# Interface.net
KiCad netlist of a schematic drawn in Altium Designer
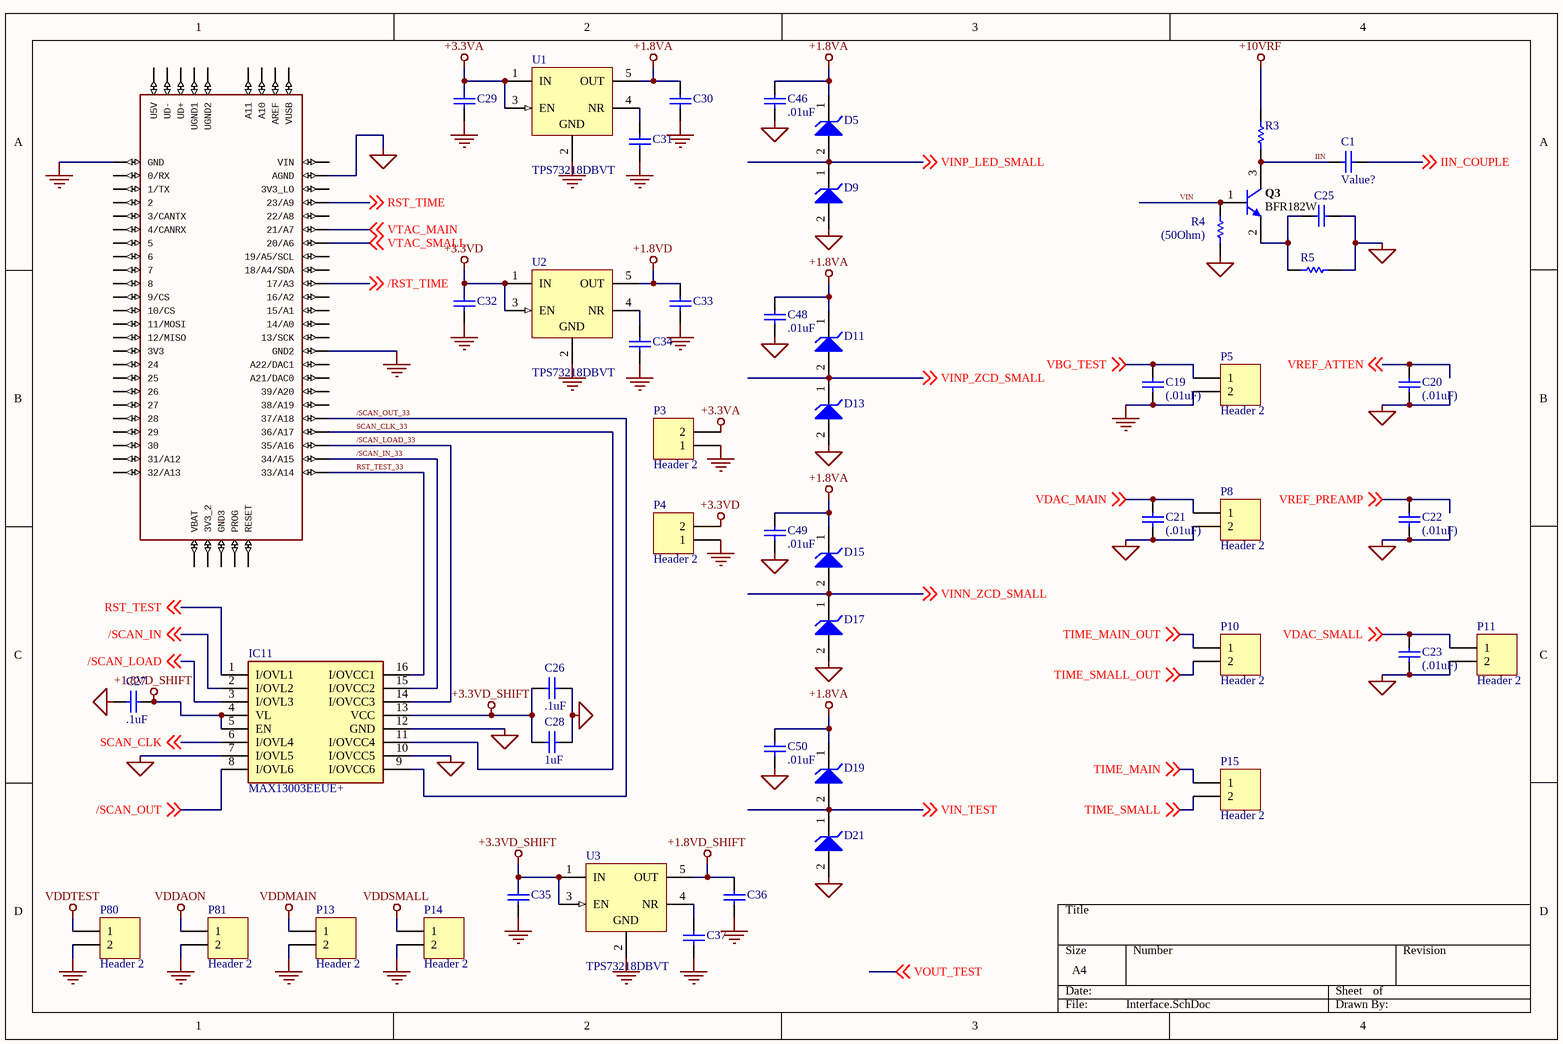
[diagram p0: Interface.SchDoc]

(export (version "E")
  (design (tool "Eeschema 10.0.6"))
  (components
    (comp (ref "1")
      (value "TEENSY_3.5/3.6")
      (footprint "TEENSY_3.5/3.6")
      (libsource (lib "Teensy356") (part "TEENSY_3.5/3.6"))
    )
    (comp (ref "C1")
      (value "Value?")
      (footprint "CAPC2013X140X45NL15T25")
      (description "0402")
      (fields (field (name "PART NUMBER") "GRM21BR71A106KE51L") (field (name "MANUFACTURER") "Murata"))
      (libsource (lib "Altium Content Vault") (part "CAP"))
    )
    (comp (ref "C19")
      (value "(.01uF)")
      (footprint "CAPC2013X140X45NL15T25")
      (description "0402")
      (fields (field (name "PART NUMBER") "GRM21BR71A106KE51L") (field (name "MANUFACTURER") "Murata"))
      (libsource (lib "Altium Content Vault") (part "CAP"))
    )
    (comp (ref "C20")
      (value "(.01uF)")
      (footprint "CAPC2013X140X45NL15T25")
      (description "0402")
      (fields (field (name "PART NUMBER") "GRM21BR71A106KE51L") (field (name "MANUFACTURER") "Murata"))
      (libsource (lib "Altium Content Vault") (part "CAP"))
    )
    (comp (ref "C21")
      (value "(.01uF)")
      (footprint "CAPC2013X140X45NL15T25")
      (description "0402")
      (fields (field (name "PART NUMBER") "GRM21BR71A106KE51L") (field (name "MANUFACTURER") "Murata"))
      (libsource (lib "Altium Content Vault") (part "CAP"))
    )
    (comp (ref "C22")
      (value "(.01uF)")
      (footprint "CAPC2013X140X45NL15T25")
      (description "0402")
      (fields (field (name "PART NUMBER") "GRM21BR71A106KE51L") (field (name "MANUFACTURER") "Murata"))
      (libsource (lib "Altium Content Vault") (part "CAP"))
    )
    (comp (ref "C23")
      (value "(.01uF)")
      (footprint "CAPC2013X140X45NL15T25")
      (description "0402")
      (fields (field (name "PART NUMBER") "GRM21BR71A106KE51L") (field (name "MANUFACTURER") "Murata"))
      (libsource (lib "Altium Content Vault") (part "CAP"))
    )
    (comp (ref "C25")
      (value "~")
      (footprint "CAPC2013X140X45NL15T25")
      (description "0402")
      (fields (field (name "PART NUMBER") "GRM21BR71A106KE51L") (field (name "MANUFACTURER") "Murata"))
      (libsource (lib "Altium Content Vault") (part "CAP"))
    )
    (comp (ref "C26")
      (value ".1uF")
      (footprint "CAPC2013X140X45NL15T25")
      (description "0402")
      (fields (field (name "PART NUMBER") "GRM21BR71A106KE51L") (field (name "MANUFACTURER") "Murata"))
      (libsource (lib "Altium Content Vault") (part "CAP"))
    )
    (comp (ref "C27")
      (value ".1uF")
      (footprint "CAPC2013X140X45NL15T25")
      (description "0402")
      (fields (field (name "PART NUMBER") "GRM21BR71A106KE51L") (field (name "MANUFACTURER") "Murata"))
      (libsource (lib "Altium Content Vault") (part "CAP"))
    )
    (comp (ref "C28")
      (value "1uF")
      (footprint "CAPC2013X140X45NL15T25")
      (description "0402")
      (fields (field (name "PART NUMBER") "GRM21BR71A106KE51L") (field (name "MANUFACTURER") "Murata"))
      (libsource (lib "Altium Content Vault") (part "CAP"))
    )
    (comp (ref "C29")
      (value "~")
      (footprint "CAPC2013X140X45NL15T25")
      (description "0402")
      (fields (field (name "PART NUMBER") "GRM21BR71A106KE51L") (field (name "MANUFACTURER") "Murata"))
      (libsource (lib "Altium Content Vault") (part "CAP"))
    )
    (comp (ref "C30")
      (value "~")
      (footprint "CAPC2013X140X45NL15T25")
      (description "0402")
      (fields (field (name "PART NUMBER") "GRM21BR71A106KE51L") (field (name "MANUFACTURER") "Murata"))
      (libsource (lib "Altium Content Vault") (part "CAP"))
    )
    (comp (ref "C31")
      (value "~")
      (footprint "CAPC2013X140X45NL15T25")
      (description "0402")
      (fields (field (name "PART NUMBER") "GRM21BR71A106KE51L") (field (name "MANUFACTURER") "Murata"))
      (libsource (lib "Altium Content Vault") (part "CAP"))
    )
    (comp (ref "C32")
      (value "~")
      (footprint "CAPC2013X140X45NL15T25")
      (description "0402")
      (fields (field (name "PART NUMBER") "GRM21BR71A106KE51L") (field (name "MANUFACTURER") "Murata"))
      (libsource (lib "Altium Content Vault") (part "CAP"))
    )
    (comp (ref "C33")
      (value "~")
      (footprint "CAPC2013X140X45NL15T25")
      (description "0402")
      (fields (field (name "PART NUMBER") "GRM21BR71A106KE51L") (field (name "MANUFACTURER") "Murata"))
      (libsource (lib "Altium Content Vault") (part "CAP"))
    )
    (comp (ref "C34")
      (value "~")
      (footprint "CAPC2013X140X45NL15T25")
      (description "0402")
      (fields (field (name "PART NUMBER") "GRM21BR71A106KE51L") (field (name "MANUFACTURER") "Murata"))
      (libsource (lib "Altium Content Vault") (part "CAP"))
    )
    (comp (ref "C35")
      (value "~")
      (footprint "CAPC2013X140X45NL15T25")
      (description "0402")
      (fields (field (name "PART NUMBER") "GRM21BR71A106KE51L") (field (name "MANUFACTURER") "Murata"))
      (libsource (lib "Altium Content Vault") (part "CAP"))
    )
    (comp (ref "C36")
      (value "~")
      (footprint "CAPC2013X140X45NL15T25")
      (description "0402")
      (fields (field (name "PART NUMBER") "GRM21BR71A106KE51L") (field (name "MANUFACTURER") "Murata"))
      (libsource (lib "Altium Content Vault") (part "CAP"))
    )
    (comp (ref "C37")
      (value "~")
      (footprint "CAPC2013X140X45NL15T25")
      (description "0402")
      (fields (field (name "PART NUMBER") "GRM21BR71A106KE51L") (field (name "MANUFACTURER") "Murata"))
      (libsource (lib "Altium Content Vault") (part "CAP"))
    )
    (comp (ref "C46")
      (value ".01uF")
      (footprint "CAPC2013X140X45NL15T25")
      (description "0402")
      (fields (field (name "PART NUMBER") "GRM21BR71A106KE51L") (field (name "MANUFACTURER") "Murata"))
      (libsource (lib "Altium Content Vault") (part "CAP"))
    )
    (comp (ref "C48")
      (value ".01uF")
      (footprint "CAPC2013X140X45NL15T25")
      (description "0402")
      (fields (field (name "PART NUMBER") "GRM21BR71A106KE51L") (field (name "MANUFACTURER") "Murata"))
      (libsource (lib "Altium Content Vault") (part "CAP"))
    )
    (comp (ref "C49")
      (value ".01uF")
      (footprint "CAPC2013X140X45NL15T25")
      (description "0402")
      (fields (field (name "PART NUMBER") "GRM21BR71A106KE51L") (field (name "MANUFACTURER") "Murata"))
      (libsource (lib "Altium Content Vault") (part "CAP"))
    )
    (comp (ref "C50")
      (value ".01uF")
      (footprint "CAPC2013X140X45NL15T25")
      (description "0402")
      (fields (field (name "PART NUMBER") "GRM21BR71A106KE51L") (field (name "MANUFACTURER") "Murata"))
      (libsource (lib "Altium Content Vault") (part "CAP"))
    )
    (comp (ref "D5")
      (value "~")
      (footprint "ONSC-SOD-123-2-425-04_V")
      (description "Zener Voltage Regulator, 2-Pin SOD-123, Pb-Free, Tape and Reel")
      (fields (field (name "MANUFACTURER") "On Semiconductor") (field (name "PARTNUMBER") "MMSZ4679T1G"))
      (libsource (lib "Altium Content Vault") (part "ONSC-K1A2-2"))
    )
    (comp (ref "D9")
      (value "~")
      (footprint "ONSC-SOD-123-2-425-04_V")
      (description "Zener Voltage Regulator, 2-Pin SOD-123, Pb-Free, Tape and Reel")
      (fields (field (name "MANUFACTURER") "On Semiconductor") (field (name "PARTNUMBER") "MMSZ4679T1G"))
      (libsource (lib "Altium Content Vault") (part "ONSC-K1A2-2"))
    )
    (comp (ref "D11")
      (value "~")
      (footprint "ONSC-SOD-123-2-425-04_V")
      (description "Zener Voltage Regulator, 2-Pin SOD-123, Pb-Free, Tape and Reel")
      (fields (field (name "MANUFACTURER") "On Semiconductor") (field (name "PARTNUMBER") "MMSZ4679T1G"))
      (libsource (lib "Altium Content Vault") (part "ONSC-K1A2-2"))
    )
    (comp (ref "D13")
      (value "~")
      (footprint "ONSC-SOD-123-2-425-04_V")
      (description "Zener Voltage Regulator, 2-Pin SOD-123, Pb-Free, Tape and Reel")
      (fields (field (name "MANUFACTURER") "On Semiconductor") (field (name "PARTNUMBER") "MMSZ4679T1G"))
      (libsource (lib "Altium Content Vault") (part "ONSC-K1A2-2"))
    )
    (comp (ref "D15")
      (value "~")
      (footprint "ONSC-SOD-123-2-425-04_V")
      (description "Zener Voltage Regulator, 2-Pin SOD-123, Pb-Free, Tape and Reel")
      (fields (field (name "MANUFACTURER") "On Semiconductor") (field (name "PARTNUMBER") "MMSZ4679T1G"))
      (libsource (lib "Altium Content Vault") (part "ONSC-K1A2-2"))
    )
    (comp (ref "D17")
      (value "~")
      (footprint "ONSC-SOD-123-2-425-04_V")
      (description "Zener Voltage Regulator, 2-Pin SOD-123, Pb-Free, Tape and Reel")
      (fields (field (name "MANUFACTURER") "On Semiconductor") (field (name "PARTNUMBER") "MMSZ4679T1G"))
      (libsource (lib "Altium Content Vault") (part "ONSC-K1A2-2"))
    )
    (comp (ref "D19")
      (value "~")
      (footprint "ONSC-SOD-123-2-425-04_V")
      (description "Zener Voltage Regulator, 2-Pin SOD-123, Pb-Free, Tape and Reel")
      (fields (field (name "MANUFACTURER") "On Semiconductor") (field (name "PARTNUMBER") "MMSZ4679T1G"))
      (libsource (lib "Altium Content Vault") (part "ONSC-K1A2-2"))
    )
    (comp (ref "D21")
      (value "~")
      (footprint "ONSC-SOD-123-2-425-04_V")
      (description "Zener Voltage Regulator, 2-Pin SOD-123, Pb-Free, Tape and Reel")
      (fields (field (name "MANUFACTURER") "On Semiconductor") (field (name "PARTNUMBER") "MMSZ4679T1G"))
      (libsource (lib "Altium Content Vault") (part "ONSC-K1A2-2"))
    )
    (comp (ref "IC11")
      (value "MAX13003EEUE+")
      (footprint "SamacSys:SOP65P640X110-16N")
      (description "Integrated Circuit")
      (libsource (lib "*") (part "MAX13003EEUE+"))
    )
    (comp (ref "P3")
      (value "Header 2")
      (footprint "HDR1X2")
      (description "Header, 2-Pin")
      (fields (field (name "PUBLISHER") "Altium Limited"))
      (libsource (lib "Miscellaneous Connectors") (part "Header 2"))
    )
    (comp (ref "P4")
      (value "Header 2")
      (footprint "HDR1X2")
      (description "Header, 2-Pin")
      (fields (field (name "PUBLISHER") "Altium Limited"))
      (libsource (lib "Miscellaneous Connectors") (part "Header 2"))
    )
    (comp (ref "P5")
      (value "Header 2")
      (footprint "HDR1X2")
      (description "Header, 2-Pin")
      (fields (field (name "PUBLISHER") "Altium Limited"))
      (libsource (lib "") (part "Header 2_1"))
    )
    (comp (ref "P8")
      (value "Header 2")
      (footprint "HDR1X2")
      (description "Header, 2-Pin")
      (fields (field (name "PUBLISHER") "Altium Limited"))
      (libsource (lib "") (part "Header 2_1"))
    )
    (comp (ref "P10")
      (value "Header 2")
      (footprint "HDR1X2")
      (description "Header, 2-Pin")
      (fields (field (name "PUBLISHER") "Altium Limited"))
      (libsource (lib "") (part "Header 2_1"))
    )
    (comp (ref "P11")
      (value "Header 2")
      (footprint "HDR1X2")
      (description "Header, 2-Pin")
      (fields (field (name "PUBLISHER") "Altium Limited"))
      (libsource (lib "") (part "Header 2_1"))
    )
    (comp (ref "P13")
      (value "Header 2")
      (footprint "HDR1X2")
      (description "Header, 2-Pin")
      (fields (field (name "PUBLISHER") "Altium Limited"))
      (libsource (lib "") (part "Header 2_1"))
    )
    (comp (ref "P14")
      (value "Header 2")
      (footprint "HDR1X2")
      (description "Header, 2-Pin")
      (fields (field (name "PUBLISHER") "Altium Limited"))
      (libsource (lib "") (part "Header 2_1"))
    )
    (comp (ref "P15")
      (value "Header 2")
      (footprint "HDR1X2")
      (description "Header, 2-Pin")
      (fields (field (name "PUBLISHER") "Altium Limited"))
      (libsource (lib "") (part "Header 2_1"))
    )
    (comp (ref "P80")
      (value "Header 2")
      (footprint "HDR1X2")
      (description "Header, 2-Pin")
      (fields (field (name "PUBLISHER") "Altium Limited"))
      (libsource (lib "") (part "Header 2_1"))
    )
    (comp (ref "P81")
      (value "Header 2")
      (footprint "HDR1X2")
      (description "Header, 2-Pin")
      (fields (field (name "PUBLISHER") "Altium Limited"))
      (libsource (lib "") (part "Header 2_1"))
    )
    (comp (ref "Q3")
      (value "BFR182W")
      (footprint "INF-SOT323_L")
      (description "NPN Silicon RF Transistor, 12 V VCEO, 35 mA IC, 19 dB Gmax, SOT323, Green")
      (fields (field (name "MANUFACTURER") "Infineon"))
      (libsource (lib "Altium Content Vault") (part "INF-BFR182W-3"))
    )
    (comp (ref "R3")
      (value "~")
      (footprint "RESC1005X40X25NL05T10")
      (description "0402")
      (fields (field (name "PART NUMBER") "RC0402FR-071KL") (field (name "MANUFACTURER") "Yageo / Phycomp"))
      (libsource (lib "Altium Content Vault") (part "RES"))
    )
    (comp (ref "R4")
      (value "(50Ohm)")
      (footprint "RESC1005X40X25NL05T10")
      (description "0402")
      (fields (field (name "PART NUMBER") "RC0402FR-071KL") (field (name "MANUFACTURER") "Yageo / Phycomp"))
      (libsource (lib "Altium Content Vault") (part "RES"))
    )
    (comp (ref "R5")
      (value "~")
      (footprint "RESC1005X40X25NL05T10")
      (description "0402")
      (fields (field (name "PART NUMBER") "RC0402FR-071KL") (field (name "MANUFACTURER") "Yageo / Phycomp"))
      (libsource (lib "Altium Content Vault") (part "RES"))
    )
    (comp (ref "U1")
      (value "TPS73218DBVT")
      (footprint "DBV0005A_N")
      (fields (field (name "MANUFACTURER") "Texas Instruments"))
      (libsource (lib "Altium Content Vault") (part "TI-TPS79NXX-YYSOT5"))
    )
    (comp (ref "U2")
      (value "TPS73218DBVT")
      (footprint "DBV0005A_N")
      (fields (field (name "MANUFACTURER") "Texas Instruments"))
      (libsource (lib "Altium Content Vault") (part "TI-TPS79NXX-YYSOT5"))
    )
    (comp (ref "U3")
      (value "TPS73218DBVT")
      (footprint "DBV0005A_N")
      (fields (field (name "MANUFACTURER") "Texas Instruments"))
      (libsource (lib "Altium Content Vault") (part "TI-TPS79NXX-YYSOT5"))
    )
  )
  (nets
    (net (code "1") (name "+1.8VA") (class "Default")
      (node (ref "C30") (pin "2") (pinfunction "2_2") (pintype "passive"))
      (node (ref "C46") (pin "2") (pinfunction "2_2") (pintype "passive"))
      (node (ref "C48") (pin "2") (pinfunction "2_2") (pintype "passive"))
      (node (ref "C49") (pin "2") (pinfunction "2_2") (pintype "passive"))
      (node (ref "C50") (pin "2") (pinfunction "2_2") (pintype "passive"))
      (node (ref "D11") (pin "1") (pinfunction "K_1") (pintype "passive"))
      (node (ref "D15") (pin "1") (pinfunction "K_1") (pintype "passive"))
      (node (ref "D19") (pin "1") (pinfunction "K_1") (pintype "passive"))
      (node (ref "D5") (pin "1") (pinfunction "K_1") (pintype "passive"))
      (node (ref "U1") (pin "5") (pinfunction "OUT_5") (pintype "power_in"))
    )
    (net (code "2") (name "+1.8VD") (class "Default")
      (node (ref "C33") (pin "2") (pinfunction "2_2") (pintype "passive"))
      (node (ref "U2") (pin "5") (pinfunction "OUT_5") (pintype "power_in"))
    )
    (net (code "3") (name "+1.8VD_SHIFT") (class "Default")
      (node (ref "C27") (pin "1") (pinfunction "1_1") (pintype "passive"))
      (node (ref "C36") (pin "2") (pinfunction "2_2") (pintype "passive"))
      (node (ref "IC11") (pin "4") (pinfunction "VL_4") (pintype "passive"))
      (node (ref "IC11") (pin "5") (pinfunction "EN_5") (pintype "passive"))
      (node (ref "U3") (pin "5") (pinfunction "OUT_5") (pintype "power_in"))
    )
    (net (code "4") (name "+3.3VA") (class "Default")
      (node (ref "C29") (pin "2") (pinfunction "2_2") (pintype "passive"))
      (node (ref "P3") (pin "2") (pinfunction "2_2") (pintype "passive"))
      (node (ref "U1") (pin "1") (pinfunction "IN_1") (pintype "power_in"))
      (node (ref "U1") (pin "3") (pinfunction "EN_3") (pintype "input"))
    )
    (net (code "5") (name "+3.3VD") (class "Default")
      (node (ref "C32") (pin "2") (pinfunction "2_2") (pintype "passive"))
      (node (ref "P4") (pin "2") (pinfunction "2_2") (pintype "passive"))
      (node (ref "U2") (pin "1") (pinfunction "IN_1") (pintype "power_in"))
      (node (ref "U2") (pin "3") (pinfunction "EN_3") (pintype "input"))
    )
    (net (code "6") (name "+3.3VD_SHIFT") (class "Default")
      (node (ref "C26") (pin "2") (pinfunction "2_2") (pintype "passive"))
      (node (ref "C28") (pin "2") (pinfunction "2_2") (pintype "passive"))
      (node (ref "C35") (pin "2") (pinfunction "2_2") (pintype "passive"))
      (node (ref "IC11") (pin "13") (pinfunction "VCC_13") (pintype "passive"))
      (node (ref "U3") (pin "1") (pinfunction "IN_1") (pintype "power_in"))
      (node (ref "U3") (pin "3") (pinfunction "EN_3") (pintype "input"))
    )
    (net (code "7") (name "+10VRF") (class "Default")
      (node (ref "R3") (pin "1") (pinfunction "1_1") (pintype "passive"))
    )
    (net (code "8") (name "/IIN") (class "Default")
      (node (ref "C1") (pin "1") (pinfunction "1_1") (pintype "passive"))
      (node (ref "Q3") (pin "3") (pinfunction "C_3") (pintype "passive"))
      (node (ref "R3") (pin "2") (pinfunction "2_2") (pintype "passive"))
    )
    (net (code "9") (name "/RST_TEST_33") (class "Default")
      (node (ref "1") (pin "33/A14") (pinfunction "33/A14_33/A14") (pintype "bidirectional"))
      (node (ref "IC11") (pin "16") (pinfunction "I/OVCC1_16") (pintype "passive"))
    )
    (net (code "10") (name "/SCAN_CLK_33") (class "Default")
      (node (ref "1") (pin "36/A17") (pinfunction "36/A17_36/A17") (pintype "bidirectional"))
      (node (ref "IC11") (pin "11") (pinfunction "I/OVCC4_11") (pintype "passive"))
    )
    (net (code "11") (name "/VIN") (class "Default")
      (node (ref "Q3") (pin "1") (pinfunction "B_1") (pintype "passive"))
      (node (ref "R4") (pin "2") (pinfunction "2_2") (pintype "passive"))
    )
    (net (code "12") (name "/{slash}SCAN_IN_33") (class "Default")
      (node (ref "1") (pin "34/A15") (pinfunction "34/A15_34/A15") (pintype "bidirectional"))
      (node (ref "IC11") (pin "15") (pinfunction "I/OVCC2_15") (pintype "passive"))
    )
    (net (code "13") (name "/{slash}SCAN_LOAD_33") (class "Default")
      (node (ref "1") (pin "35/A16") (pinfunction "35/A16_35/A16") (pintype "bidirectional"))
      (node (ref "IC11") (pin "14") (pinfunction "I/OVCC3_14") (pintype "passive"))
    )
    (net (code "14") (name "/{slash}SCAN_OUT_33") (class "Default")
      (node (ref "1") (pin "37/A18") (pinfunction "37/A18_37/A18") (pintype "bidirectional"))
      (node (ref "IC11") (pin "9") (pinfunction "I/OVCC6_9") (pintype "passive"))
    )
    (net (code "15") (name "GND") (class "Default")
      (node (ref "1") (pin "AGND") (pinfunction "AGND_AGND") (pintype "bidirectional"))
      (node (ref "1") (pin "GND") (pinfunction "GND_GND") (pintype "bidirectional"))
      (node (ref "1") (pin "GND2") (pinfunction "GND2_GND2") (pintype "bidirectional"))
      (node (ref "C19") (pin "1") (pinfunction "1_1") (pintype "passive"))
      (node (ref "C20") (pin "1") (pinfunction "1_1") (pintype "passive"))
      (node (ref "C21") (pin "1") (pinfunction "1_1") (pintype "passive"))
      (node (ref "C22") (pin "1") (pinfunction "1_1") (pintype "passive"))
      (node (ref "C23") (pin "1") (pinfunction "1_1") (pintype "passive"))
      (node (ref "C25") (pin "1") (pinfunction "1_1") (pintype "passive"))
      (node (ref "C26") (pin "1") (pinfunction "1_1") (pintype "passive"))
      (node (ref "C27") (pin "2") (pinfunction "2_2") (pintype "passive"))
      (node (ref "C28") (pin "1") (pinfunction "1_1") (pintype "passive"))
      (node (ref "C29") (pin "1") (pinfunction "1_1") (pintype "passive"))
      (node (ref "C30") (pin "1") (pinfunction "1_1") (pintype "passive"))
      (node (ref "C31") (pin "1") (pinfunction "1_1") (pintype "passive"))
      (node (ref "C32") (pin "1") (pinfunction "1_1") (pintype "passive"))
      (node (ref "C33") (pin "1") (pinfunction "1_1") (pintype "passive"))
      (node (ref "C34") (pin "1") (pinfunction "1_1") (pintype "passive"))
      (node (ref "C35") (pin "1") (pinfunction "1_1") (pintype "passive"))
      (node (ref "C36") (pin "1") (pinfunction "1_1") (pintype "passive"))
      (node (ref "C37") (pin "1") (pinfunction "1_1") (pintype "passive"))
      (node (ref "C46") (pin "1") (pinfunction "1_1") (pintype "passive"))
      (node (ref "C48") (pin "1") (pinfunction "1_1") (pintype "passive"))
      (node (ref "C49") (pin "1") (pinfunction "1_1") (pintype "passive"))
      (node (ref "C50") (pin "1") (pinfunction "1_1") (pintype "passive"))
      (node (ref "D13") (pin "2") (pinfunction "A_2") (pintype "passive"))
      (node (ref "D17") (pin "2") (pinfunction "A_2") (pintype "passive"))
      (node (ref "D21") (pin "2") (pinfunction "A_2") (pintype "passive"))
      (node (ref "D9") (pin "2") (pinfunction "A_2") (pintype "passive"))
      (node (ref "IC11") (pin "10") (pinfunction "I/OVCC5_10") (pintype "passive"))
      (node (ref "IC11") (pin "12") (pinfunction "GND_12") (pintype "passive"))
      (node (ref "IC11") (pin "7") (pinfunction "I/OVL5_7") (pintype "passive"))
      (node (ref "P11") (pin "2") (pinfunction "2_2") (pintype "passive"))
      (node (ref "P13") (pin "2") (pinfunction "2_2") (pintype "passive"))
      (node (ref "P14") (pin "2") (pinfunction "2_2") (pintype "passive"))
      (node (ref "P3") (pin "1") (pinfunction "1_1") (pintype "passive"))
      (node (ref "P4") (pin "1") (pinfunction "1_1") (pintype "passive"))
      (node (ref "P5") (pin "2") (pinfunction "2_2") (pintype "passive"))
      (node (ref "P8") (pin "2") (pinfunction "2_2") (pintype "passive"))
      (node (ref "P80") (pin "2") (pinfunction "2_2") (pintype "passive"))
      (node (ref "P81") (pin "2") (pinfunction "2_2") (pintype "passive"))
      (node (ref "R4") (pin "1") (pinfunction "1_1") (pintype "passive"))
      (node (ref "R5") (pin "1") (pinfunction "1_1") (pintype "passive"))
      (node (ref "U1") (pin "2") (pinfunction "GND_2") (pintype "power_in"))
      (node (ref "U2") (pin "2") (pinfunction "GND_2") (pintype "power_in"))
      (node (ref "U3") (pin "2") (pinfunction "GND_2") (pintype "power_in"))
    )
    (net (code "16") (name "IIN_COUPLE") (class "Default")
      (node (ref "C1") (pin "2") (pinfunction "2_2") (pintype "passive"))
    )
    (net (code "17") (name "Net-(Q3-E)") (class "Default")
      (node (ref "C25") (pin "2") (pinfunction "2_2") (pintype "passive"))
      (node (ref "Q3") (pin "2") (pinfunction "E_2") (pintype "passive"))
      (node (ref "R5") (pin "2") (pinfunction "2_2") (pintype "passive"))
    )
    (net (code "18") (name "Net-(U1-NR)") (class "Default")
      (node (ref "C31") (pin "2") (pinfunction "2_2") (pintype "passive"))
      (node (ref "U1") (pin "4") (pinfunction "NR_4") (pintype "passive"))
    )
    (net (code "19") (name "Net-(U2-NR)") (class "Default")
      (node (ref "C34") (pin "2") (pinfunction "2_2") (pintype "passive"))
      (node (ref "U2") (pin "4") (pinfunction "NR_4") (pintype "passive"))
    )
    (net (code "20") (name "Net-(U3-NR)") (class "Default")
      (node (ref "C37") (pin "2") (pinfunction "2_2") (pintype "passive"))
      (node (ref "U3") (pin "4") (pinfunction "NR_4") (pintype "passive"))
    )
    (net (code "21") (name "RST_TEST") (class "Default")
      (node (ref "IC11") (pin "1") (pinfunction "I/OVL1_1") (pintype "passive"))
    )
    (net (code "22") (name "RST_TIME") (class "Default")
      (node (ref "1") (pin "23/A9") (pinfunction "23/A9_23/A9") (pintype "bidirectional"))
    )
    (net (code "23") (name "SCAN_CLK") (class "Default")
      (node (ref "IC11") (pin "6") (pinfunction "I/OVL4_6") (pintype "passive"))
    )
    (net (code "24") (name "TIME_MAIN") (class "Default")
      (node (ref "P15") (pin "1") (pinfunction "1_1") (pintype "passive"))
    )
    (net (code "25") (name "TIME_MAIN_OUT") (class "Default")
      (node (ref "P10") (pin "1") (pinfunction "1_1") (pintype "passive"))
    )
    (net (code "26") (name "TIME_SMALL") (class "Default")
      (node (ref "P15") (pin "2") (pinfunction "2_2") (pintype "passive"))
    )
    (net (code "27") (name "TIME_SMALL_OUT") (class "Default")
      (node (ref "P10") (pin "2") (pinfunction "2_2") (pintype "passive"))
    )
    (net (code "28") (name "VBG_TEST") (class "Default")
      (node (ref "C19") (pin "2") (pinfunction "2_2") (pintype "passive"))
      (node (ref "P5") (pin "1") (pinfunction "1_1") (pintype "passive"))
    )
    (net (code "29") (name "VDAC_MAIN") (class "Default")
      (node (ref "C21") (pin "2") (pinfunction "2_2") (pintype "passive"))
      (node (ref "P8") (pin "1") (pinfunction "1_1") (pintype "passive"))
    )
    (net (code "30") (name "VDAC_SMALL") (class "Default")
      (node (ref "C23") (pin "2") (pinfunction "2_2") (pintype "passive"))
      (node (ref "P11") (pin "1") (pinfunction "1_1") (pintype "passive"))
    )
    (net (code "31") (name "VDDAON") (class "Default")
      (node (ref "P81") (pin "1") (pinfunction "1_1") (pintype "passive"))
    )
    (net (code "32") (name "VDDMAIN") (class "Default")
      (node (ref "P13") (pin "1") (pinfunction "1_1") (pintype "passive"))
    )
    (net (code "33") (name "VDDSMALL") (class "Default")
      (node (ref "P14") (pin "1") (pinfunction "1_1") (pintype "passive"))
    )
    (net (code "34") (name "VDDTEST") (class "Default")
      (node (ref "P80") (pin "1") (pinfunction "1_1") (pintype "passive"))
    )
    (net (code "35") (name "VINN_ZCD_SMALL") (class "Default")
      (node (ref "D15") (pin "2") (pinfunction "A_2") (pintype "passive"))
      (node (ref "D17") (pin "1") (pinfunction "K_1") (pintype "passive"))
    )
    (net (code "36") (name "VINP_LED_SMALL") (class "Default")
      (node (ref "D5") (pin "2") (pinfunction "A_2") (pintype "passive"))
      (node (ref "D9") (pin "1") (pinfunction "K_1") (pintype "passive"))
    )
    (net (code "37") (name "VINP_ZCD_SMALL") (class "Default")
      (node (ref "D11") (pin "2") (pinfunction "A_2") (pintype "passive"))
      (node (ref "D13") (pin "1") (pinfunction "K_1") (pintype "passive"))
    )
    (net (code "38") (name "VIN_TEST") (class "Default")
      (node (ref "D19") (pin "2") (pinfunction "A_2") (pintype "passive"))
      (node (ref "D21") (pin "1") (pinfunction "K_1") (pintype "passive"))
    )
    (net (code "40") (name "VREF_ATTEN") (class "Default")
      (node (ref "C20") (pin "2") (pinfunction "2_2") (pintype "passive"))
    )
    (net (code "41") (name "VREF_PREAMP") (class "Default")
      (node (ref "C22") (pin "2") (pinfunction "2_2") (pintype "passive"))
    )
    (net (code "42") (name "VTAC_MAIN") (class "Default")
      (node (ref "1") (pin "21/A7") (pinfunction "21/A7_21/A7") (pintype "bidirectional"))
    )
    (net (code "43") (name "VTAC_SMALL") (class "Default")
      (node (ref "1") (pin "20/A6") (pinfunction "20/A6_20/A6") (pintype "bidirectional"))
    )
    (net (code "44") (name "unconnected-(1-A21{slash}DAC0-Pad21{slash}DAC0)") (class "Default")
      (node (ref "1") (pin "21/DAC0") (pinfunction "A21/DAC0_21/DAC0") (pintype "bidirectional"))
    )
    (net (code "45") (name "unconnected-(1-Pad0{slash}RX)") (class "Default")
      (node (ref "1") (pin "0/RX") (pinfunction "0/RX_0/RX") (pintype "bidirectional"))
    )
    (net (code "46") (name "unconnected-(1-Pad1{slash}TX)") (class "Default")
      (node (ref "1") (pin "1/TX") (pinfunction "1/TX_1/TX") (pintype "bidirectional"))
    )
    (net (code "47") (name "unconnected-(1-Pad2)") (class "Default")
      (node (ref "1") (pin "2") (pinfunction "2_2") (pintype "bidirectional"))
    )
    (net (code "48") (name "unconnected-(1-Pad3V3)") (class "Default")
      (node (ref "1") (pin "3V3") (pinfunction "3V3_3V3") (pintype "bidirectional"))
    )
    (net (code "49") (name "unconnected-(1-Pad3V3_2)") (class "Default")
      (node (ref "1") (pin "3V3_2") (pinfunction "3V3_2_3V3_2") (pintype "bidirectional"))
    )
    (net (code "50") (name "unconnected-(1-Pad3V3_LO)") (class "Default")
      (node (ref "1") (pin "3V3_LO") (pinfunction "3V3_LO_3V3_LO") (pintype "bidirectional"))
    )
    (net (code "51") (name "unconnected-(1-Pad3{slash}CANTX)") (class "Default")
      (node (ref "1") (pin "3/CANTX") (pinfunction "3/CANTX_3/CANTX") (pintype "bidirectional"))
    )
    (net (code "52") (name "unconnected-(1-Pad4{slash}CANRX)") (class "Default")
      (node (ref "1") (pin "4/CANRX") (pinfunction "4/CANRX_4/CANRX") (pintype "bidirectional"))
    )
    (net (code "53") (name "unconnected-(1-Pad5)") (class "Default")
      (node (ref "1") (pin "5") (pinfunction "5_5") (pintype "bidirectional"))
    )
    (net (code "54") (name "unconnected-(1-Pad6)") (class "Default")
      (node (ref "1") (pin "6") (pinfunction "6_6") (pintype "bidirectional"))
    )
    (net (code "55") (name "unconnected-(1-Pad7)") (class "Default")
      (node (ref "1") (pin "7") (pinfunction "7_7") (pintype "bidirectional"))
    )
    (net (code "56") (name "unconnected-(1-Pad8)") (class "Default")
      (node (ref "1") (pin "8") (pinfunction "8_8") (pintype "bidirectional"))
    )
    (net (code "57") (name "unconnected-(1-Pad9{slash}CS)") (class "Default")
      (node (ref "1") (pin "9/CS") (pinfunction "9/CS_9/CS") (pintype "bidirectional"))
    )
    (net (code "58") (name "unconnected-(1-Pad10{slash}CS)") (class "Default")
      (node (ref "1") (pin "10/CS") (pinfunction "10/CS_10/CS") (pintype "bidirectional"))
    )
    (net (code "59") (name "unconnected-(1-Pad11{slash}MOSI)") (class "Default")
      (node (ref "1") (pin "11/MOSI") (pinfunction "11/MOSI_11/MOSI") (pintype "bidirectional"))
    )
    (net (code "60") (name "unconnected-(1-Pad12{slash}MISO)") (class "Default")
      (node (ref "1") (pin "12/MISO") (pinfunction "12/MISO_12/MISO") (pintype "bidirectional"))
    )
    (net (code "61") (name "unconnected-(1-Pad13{slash}SCK)") (class "Default")
      (node (ref "1") (pin "13/SCK") (pinfunction "13/SCK_13/SCK") (pintype "bidirectional"))
    )
    (net (code "62") (name "unconnected-(1-Pad14{slash}A0)") (class "Default")
      (node (ref "1") (pin "14/A0") (pinfunction "14/A0_14/A0") (pintype "bidirectional"))
    )
    (net (code "63") (name "unconnected-(1-Pad15{slash}A1)") (class "Default")
      (node (ref "1") (pin "15/A1") (pinfunction "15/A1_15/A1") (pintype "bidirectional"))
    )
    (net (code "64") (name "unconnected-(1-Pad16{slash}A2)") (class "Default")
      (node (ref "1") (pin "16/A2") (pinfunction "16/A2_16/A2") (pintype "bidirectional"))
    )
    (net (code "65") (name "unconnected-(1-Pad18{slash}A4{slash}SDA)") (class "Default")
      (node (ref "1") (pin "18/A4/SDA") (pinfunction "18/A4/SDA_18/A4/SDA") (pintype "bidirectional"))
    )
    (net (code "66") (name "unconnected-(1-Pad19{slash}A5{slash}SCL)") (class "Default")
      (node (ref "1") (pin "19/A5/SCL") (pinfunction "19/A5/SCL_19/A5/SCL") (pintype "bidirectional"))
    )
    (net (code "67") (name "unconnected-(1-Pad22{slash}A8)") (class "Default")
      (node (ref "1") (pin "22/A8") (pinfunction "22/A8_22/A8") (pintype "bidirectional"))
    )
    (net (code "68") (name "unconnected-(1-Pad24)") (class "Default")
      (node (ref "1") (pin "24") (pinfunction "24_24") (pintype "bidirectional"))
    )
    (net (code "69") (name "unconnected-(1-Pad25)") (class "Default")
      (node (ref "1") (pin "25") (pinfunction "25_25") (pintype "bidirectional"))
    )
    (net (code "70") (name "unconnected-(1-Pad26)") (class "Default")
      (node (ref "1") (pin "26") (pinfunction "26_26") (pintype "bidirectional"))
    )
    (net (code "71") (name "unconnected-(1-Pad27)") (class "Default")
      (node (ref "1") (pin "27") (pinfunction "27_27") (pintype "bidirectional"))
    )
    (net (code "72") (name "unconnected-(1-Pad28)") (class "Default")
      (node (ref "1") (pin "28") (pinfunction "28_28") (pintype "bidirectional"))
    )
    (net (code "73") (name "unconnected-(1-Pad29)") (class "Default")
      (node (ref "1") (pin "29") (pinfunction "29_29") (pintype "bidirectional"))
    )
    (net (code "74") (name "unconnected-(1-Pad30)") (class "Default")
      (node (ref "1") (pin "30") (pinfunction "30_30") (pintype "bidirectional"))
    )
    (net (code "75") (name "unconnected-(1-Pad31{slash}A12)") (class "Default")
      (node (ref "1") (pin "31/A12") (pinfunction "31/A12_31/A12") (pintype "bidirectional"))
    )
    (net (code "76") (name "unconnected-(1-Pad32{slash}A13)") (class "Default")
      (node (ref "1") (pin "32/A13") (pinfunction "32/A13_32/A13") (pintype "bidirectional"))
    )
    (net (code "77") (name "unconnected-(1-Pad38{slash}A19)") (class "Default")
      (node (ref "1") (pin "38/A19") (pinfunction "38/A19_38/A19") (pintype "bidirectional"))
    )
    (net (code "78") (name "unconnected-(1-Pad39{slash}A20)") (class "Default")
      (node (ref "1") (pin "39/A20") (pinfunction "39/A20_39/A20") (pintype "bidirectional"))
    )
    (net (code "79") (name "unconnected-(1-PadA10)") (class "Default")
      (node (ref "1") (pin "A10") (pinfunction "A10_A10") (pintype "bidirectional"))
    )
    (net (code "80") (name "unconnected-(1-PadA11)") (class "Default")
      (node (ref "1") (pin "A11") (pinfunction "A11_A11") (pintype "bidirectional"))
    )
    (net (code "81") (name "unconnected-(1-PadA22{slash}DAC1)") (class "Default")
      (node (ref "1") (pin "A22/DAC1") (pinfunction "A22/DAC1_A22/DAC1") (pintype "bidirectional"))
    )
    (net (code "82") (name "unconnected-(1-PadAREF)") (class "Default")
      (node (ref "1") (pin "AREF") (pinfunction "AREF_AREF") (pintype "bidirectional"))
    )
    (net (code "83") (name "unconnected-(1-PadGND3)") (class "Default")
      (node (ref "1") (pin "GND3") (pinfunction "GND3_GND3") (pintype "bidirectional"))
    )
    (net (code "84") (name "unconnected-(1-PadPROG)") (class "Default")
      (node (ref "1") (pin "PROG") (pinfunction "PROG_PROG") (pintype "bidirectional"))
    )
    (net (code "85") (name "unconnected-(1-PadRESET)") (class "Default")
      (node (ref "1") (pin "RESET") (pinfunction "RESET_RESET") (pintype "bidirectional"))
    )
    (net (code "86") (name "unconnected-(1-PadU5V)") (class "Default")
      (node (ref "1") (pin "U5V") (pinfunction "U5V_U5V") (pintype "bidirectional"))
    )
    (net (code "87") (name "unconnected-(1-PadUD+)") (class "Default")
      (node (ref "1") (pin "UD+") (pinfunction "UD+_UD+") (pintype "bidirectional"))
    )
    (net (code "88") (name "unconnected-(1-PadUD-)") (class "Default")
      (node (ref "1") (pin "UD-") (pinfunction "UD-_UD-") (pintype "bidirectional"))
    )
    (net (code "89") (name "unconnected-(1-PadUGND1)") (class "Default")
      (node (ref "1") (pin "UGND1") (pinfunction "UGND1_UGND1") (pintype "bidirectional"))
    )
    (net (code "90") (name "unconnected-(1-PadUGND2)") (class "Default")
      (node (ref "1") (pin "UGND2") (pinfunction "UGND2_UGND2") (pintype "bidirectional"))
    )
    (net (code "91") (name "unconnected-(1-PadVBAT)") (class "Default")
      (node (ref "1") (pin "VBAT") (pinfunction "VBAT_VBAT") (pintype "bidirectional"))
    )
    (net (code "92") (name "unconnected-(1-PadVIN)") (class "Default")
      (node (ref "1") (pin "VIN") (pinfunction "VIN_VIN") (pintype "bidirectional"))
    )
    (net (code "93") (name "unconnected-(1-PadVUSB)") (class "Default")
      (node (ref "1") (pin "VUSB") (pinfunction "VUSB_VUSB") (pintype "bidirectional"))
    )
    (net (code "94") (name "{slash}RST_TIME") (class "Default")
      (node (ref "1") (pin "17/A3") (pinfunction "17/A3_17/A3") (pintype "bidirectional"))
    )
    (net (code "95") (name "{slash}SCAN_IN") (class "Default")
      (node (ref "IC11") (pin "2") (pinfunction "I/OVL2_2") (pintype "passive"))
    )
    (net (code "96") (name "{slash}SCAN_LOAD") (class "Default")
      (node (ref "IC11") (pin "3") (pinfunction "I/OVL3_3") (pintype "passive"))
    )
    (net (code "97") (name "{slash}SCAN_OUT") (class "Default")
      (node (ref "IC11") (pin "8") (pinfunction "I/OVL6_8") (pintype "passive"))
    )
  )
)
